# enc_ma710.net
KiCad netlist of a schematic drawn in EAGLE
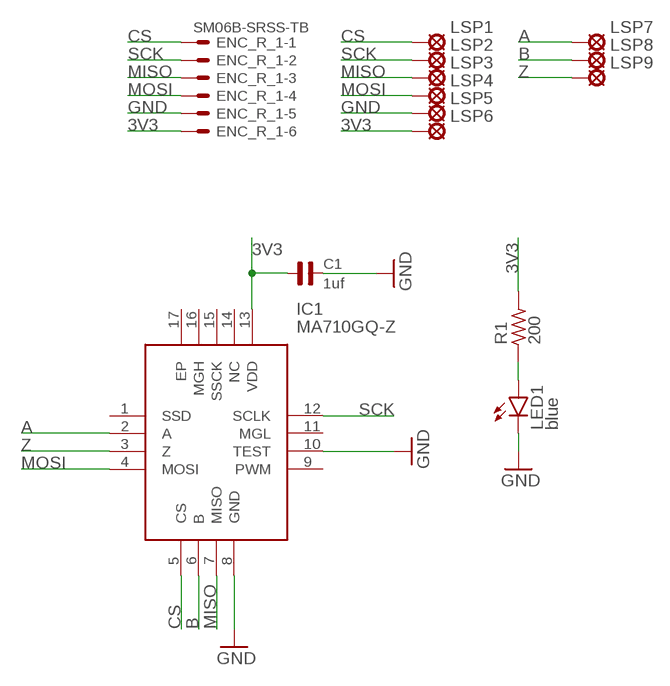
[diagram p0: schematic, sheet 1]

(export (version "E")
  (design (tool "Eeschema 10.0.6"))
  (components
    (comp (ref "C1")
      (value "1uf")
      (footprint "eagle-import:0603")
      (libsource (lib "eagle-import") (part "C0603"))
    )
    (comp (ref "ENC_R_1")
      (value "SM06B-SRSS-TB")
      (footprint "eagle-import:SM06B-SRSS-TB")
      (libsource (lib "eagle-import") (part "?M06B-SRSS-TBS"))
    )
    (comp (ref "IC1")
      (value "MA710GQ-Z")
      (footprint "eagle-import:QFN50P300X300X100-17N")
      (fields (field (name "MOUSER_PART_NUMBER") "946-MA710GQ-Z"))
      (libsource (lib "eagle-import") (part "MA710GQ-Z"))
    )
    (comp (ref "LED1")
      (value "blue")
      (footprint "eagle-import:SML0603")
      (libsource (lib "eagle-import") (part "LEDSML0603"))
    )
    (comp (ref "LSP1")
      (value "LSP10")
      (footprint "eagle-import:LSP10")
      (libsource (lib "eagle-import") (part "LSP10"))
    )
    (comp (ref "LSP2")
      (value "LSP10")
      (footprint "eagle-import:LSP10")
      (libsource (lib "eagle-import") (part "LSP10"))
    )
    (comp (ref "LSP3")
      (value "LSP10")
      (footprint "eagle-import:LSP10")
      (libsource (lib "eagle-import") (part "LSP10"))
    )
    (comp (ref "LSP4")
      (value "LSP10")
      (footprint "eagle-import:LSP10")
      (libsource (lib "eagle-import") (part "LSP10"))
    )
    (comp (ref "LSP5")
      (value "LSP10")
      (footprint "eagle-import:LSP10")
      (libsource (lib "eagle-import") (part "LSP10"))
    )
    (comp (ref "LSP6")
      (value "LSP10")
      (footprint "eagle-import:LSP10")
      (libsource (lib "eagle-import") (part "LSP10"))
    )
    (comp (ref "LSP7")
      (value "LSP10")
      (footprint "eagle-import:LSP10")
      (libsource (lib "eagle-import") (part "LSP10"))
    )
    (comp (ref "LSP8")
      (value "LSP10")
      (footprint "eagle-import:LSP10")
      (libsource (lib "eagle-import") (part "LSP10"))
    )
    (comp (ref "LSP9")
      (value "LSP10")
      (footprint "eagle-import:LSP10")
      (libsource (lib "eagle-import") (part "LSP10"))
    )
    (comp (ref "R1")
      (value "200")
      (footprint "eagle-import:R0603")
      (libsource (lib "eagle-import") (part "R_0603"))
    )
  )
  (nets
    (net (code "1") (name "/3V3") (class "Default")
      (node (ref "C1") (pin "1") (pinfunction "1_1") (pintype "passive"))
      (node (ref "ENC_R_1") (pin "6") (pinfunction "S_6") (pintype "passive"))
      (node (ref "IC1") (pin "13") (pinfunction "VDD_13") (pintype "bidirectional"))
      (node (ref "LSP6") (pin "MP") (pinfunction "MP_MP") (pintype "passive"))
      (node (ref "R1") (pin "2") (pinfunction "2_2") (pintype "passive"))
    )
    (net (code "2") (name "/A") (class "Default")
      (node (ref "IC1") (pin "2") (pinfunction "A_2") (pintype "bidirectional"))
      (node (ref "LSP7") (pin "MP") (pinfunction "MP_MP") (pintype "passive"))
    )
    (net (code "3") (name "/B") (class "Default")
      (node (ref "IC1") (pin "6") (pinfunction "B_6") (pintype "bidirectional"))
      (node (ref "LSP8") (pin "MP") (pinfunction "MP_MP") (pintype "passive"))
    )
    (net (code "4") (name "/CS") (class "Default")
      (node (ref "ENC_R_1") (pin "1") (pinfunction "S_1") (pintype "passive"))
      (node (ref "IC1") (pin "5") (pinfunction "CS_5") (pintype "bidirectional"))
      (node (ref "LSP1") (pin "MP") (pinfunction "MP_MP") (pintype "passive"))
    )
    (net (code "5") (name "/MISO") (class "Default")
      (node (ref "ENC_R_1") (pin "3") (pinfunction "S_3") (pintype "passive"))
      (node (ref "IC1") (pin "7") (pinfunction "MISO_7") (pintype "bidirectional"))
      (node (ref "LSP3") (pin "MP") (pinfunction "MP_MP") (pintype "passive"))
    )
    (net (code "6") (name "/MOSI") (class "Default")
      (node (ref "ENC_R_1") (pin "4") (pinfunction "S_4") (pintype "passive"))
      (node (ref "IC1") (pin "4") (pinfunction "MOSI_4") (pintype "bidirectional"))
      (node (ref "LSP4") (pin "MP") (pinfunction "MP_MP") (pintype "passive"))
    )
    (net (code "7") (name "/SCK") (class "Default")
      (node (ref "ENC_R_1") (pin "2") (pinfunction "S_2") (pintype "passive"))
      (node (ref "IC1") (pin "12") (pinfunction "SCLK_12") (pintype "bidirectional"))
      (node (ref "LSP2") (pin "MP") (pinfunction "MP_MP") (pintype "passive"))
    )
    (net (code "8") (name "/Z") (class "Default")
      (node (ref "IC1") (pin "3") (pinfunction "Z_3") (pintype "bidirectional"))
      (node (ref "LSP9") (pin "MP") (pinfunction "MP_MP") (pintype "passive"))
    )
    (net (code "9") (name "GND") (class "Default")
      (node (ref "C1") (pin "2") (pinfunction "2_2") (pintype "passive"))
      (node (ref "ENC_R_1") (pin "5") (pinfunction "S_5") (pintype "passive"))
      (node (ref "IC1") (pin "10") (pinfunction "TEST_10") (pintype "bidirectional"))
      (node (ref "IC1") (pin "8") (pinfunction "GND_8") (pintype "bidirectional"))
      (node (ref "LED1") (pin "C") (pinfunction "C_C") (pintype "passive"))
      (node (ref "LSP5") (pin "MP") (pinfunction "MP_MP") (pintype "passive"))
    )
    (net (code "10") (name "Net-(LED1-PadA)") (class "Default")
      (node (ref "LED1") (pin "A") (pinfunction "A_A") (pintype "passive"))
      (node (ref "R1") (pin "1") (pinfunction "1_1") (pintype "passive"))
    )
    (net (code "11") (name "unconnected-(IC1-EP-Pad17)") (class "Default")
      (node (ref "IC1") (pin "17") (pinfunction "EP_17") (pintype "bidirectional"))
    )
    (net (code "12") (name "unconnected-(IC1-MGH-Pad16)") (class "Default")
      (node (ref "IC1") (pin "16") (pinfunction "MGH_16") (pintype "bidirectional"))
    )
    (net (code "13") (name "unconnected-(IC1-MGL-Pad11)") (class "Default")
      (node (ref "IC1") (pin "11") (pinfunction "MGL_11") (pintype "bidirectional"))
    )
    (net (code "14") (name "unconnected-(IC1-NC-Pad14)") (class "Default")
      (node (ref "IC1") (pin "14") (pinfunction "NC_14") (pintype "no_connect"))
    )
    (net (code "15") (name "unconnected-(IC1-PWM-Pad9)") (class "Default")
      (node (ref "IC1") (pin "9") (pinfunction "PWM_9") (pintype "bidirectional"))
    )
    (net (code "16") (name "unconnected-(IC1-SSCK-Pad15)") (class "Default")
      (node (ref "IC1") (pin "15") (pinfunction "SSCK_15") (pintype "bidirectional"))
    )
    (net (code "17") (name "unconnected-(IC1-SSD-Pad1)") (class "Default")
      (node (ref "IC1") (pin "1") (pinfunction "SSD_1") (pintype "bidirectional"))
    )
  )
)
